# Mergen_Ground_Station_V2_0.net
KiCad netlist of a schematic drawn in EAGLE
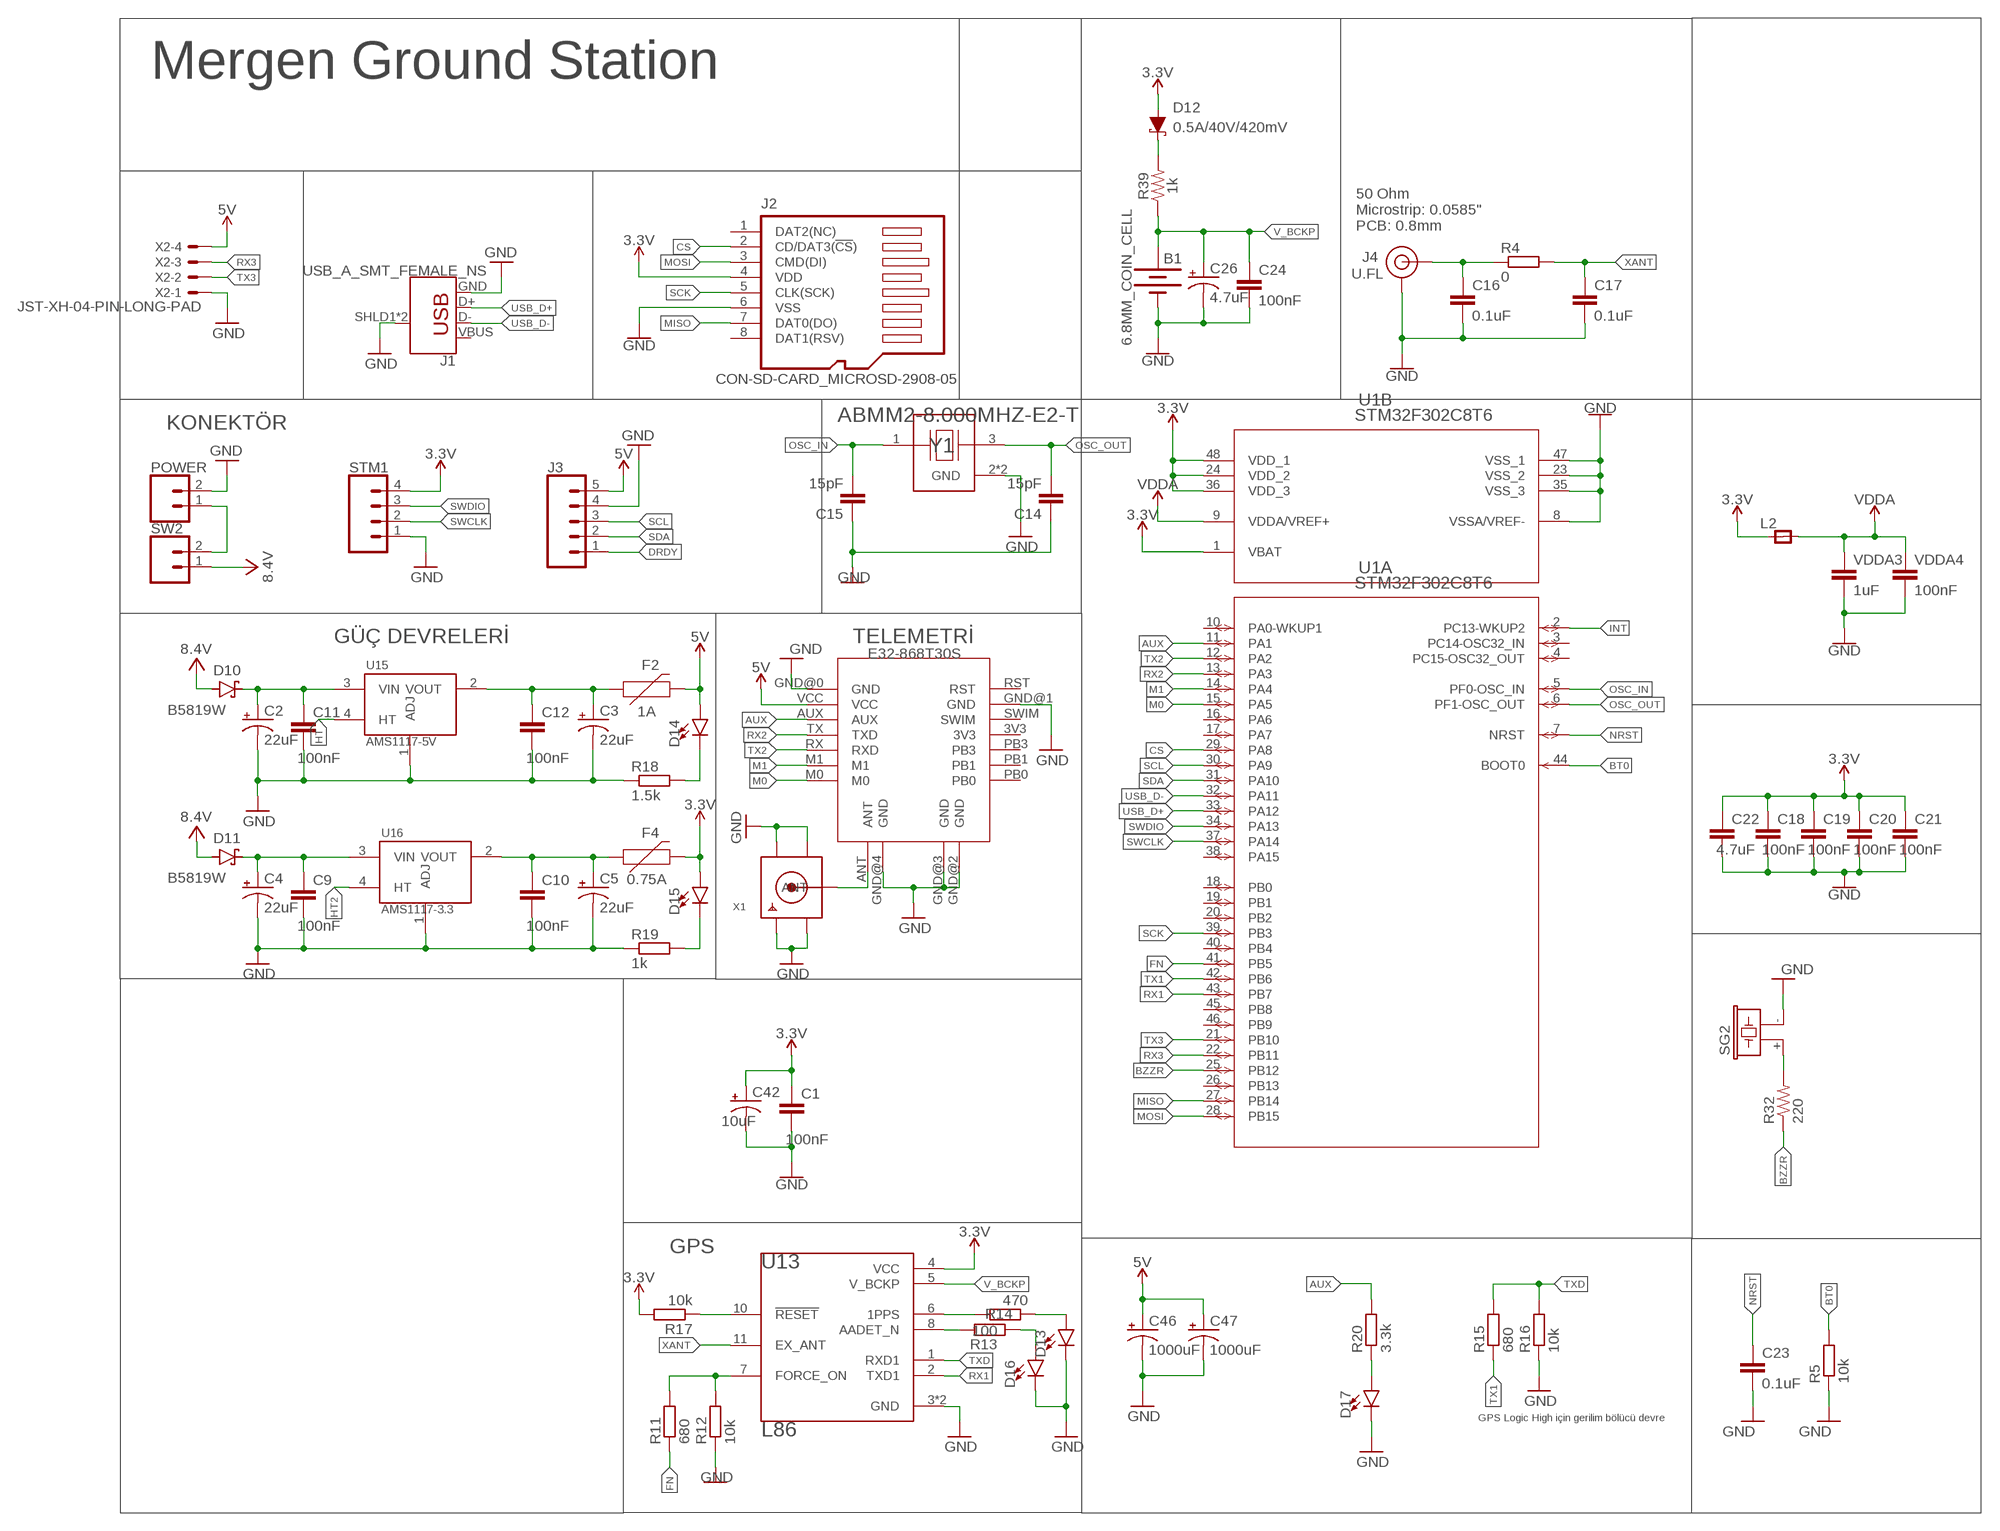
[diagram p0: schematic, sheet 1]

(export (version "E")
  (design (tool "Eeschema 10.0.6"))
  (components
    (comp (ref "B1")
      (value "6.8MM_COIN_CELL")
      (footprint "eagle-import:BATTCON-6.8MM")
      (libsource (lib "eagle-import") (part "BATTERY-6.8MM_SMD"))
    )
    (comp (ref "C1")
      (value "100nF")
      (footprint "eagle-import:C0603")
      (libsource (lib "eagle-import") (part "C-EUC0603"))
    )
    (comp (ref "C2")
      (value "22uF")
      (footprint "eagle-import:CT3528")
      (libsource (lib "eagle-import") (part "rcl_334_CPOL-USCT3528"))
    )
    (comp (ref "C3")
      (value "22uF")
      (footprint "eagle-import:CT3528")
      (libsource (lib "eagle-import") (part "rcl_334_CPOL-USCT3528"))
    )
    (comp (ref "C4")
      (value "22uF")
      (footprint "eagle-import:CT3528")
      (libsource (lib "eagle-import") (part "rcl_334_CPOL-USCT3528"))
    )
    (comp (ref "C5")
      (value "22uF")
      (footprint "eagle-import:CT3528")
      (libsource (lib "eagle-import") (part "rcl_334_CPOL-USCT3528"))
    )
    (comp (ref "C9")
      (value "100nF")
      (footprint "eagle-import:C0603")
      (libsource (lib "eagle-import") (part "C-EUC0603"))
    )
    (comp (ref "C10")
      (value "100nF")
      (footprint "eagle-import:C0603")
      (libsource (lib "eagle-import") (part "C-EUC0603"))
    )
    (comp (ref "C11")
      (value "100nF")
      (footprint "eagle-import:C0603")
      (libsource (lib "eagle-import") (part "C-EUC0603"))
    )
    (comp (ref "C12")
      (value "100nF")
      (footprint "eagle-import:C0603")
      (libsource (lib "eagle-import") (part "C-EUC0603"))
    )
    (comp (ref "C14")
      (value "15pF")
      (footprint "eagle-import:C0603")
      (libsource (lib "eagle-import") (part "C-EUC0603"))
    )
    (comp (ref "C15")
      (value "15pF")
      (footprint "eagle-import:C0603")
      (libsource (lib "eagle-import") (part "C-EUC0603"))
    )
    (comp (ref "C16")
      (value "0.1uF")
      (footprint "eagle-import:C0603")
      (libsource (lib "eagle-import") (part "C-EUC0603"))
    )
    (comp (ref "C17")
      (value "0.1uF")
      (footprint "eagle-import:C0603")
      (libsource (lib "eagle-import") (part "C-EUC0603"))
    )
    (comp (ref "C18")
      (value "100nF")
      (footprint "eagle-import:C0603")
      (libsource (lib "eagle-import") (part "C-EUC0603"))
    )
    (comp (ref "C19")
      (value "100nF")
      (footprint "eagle-import:C0603")
      (libsource (lib "eagle-import") (part "C-EUC0603"))
    )
    (comp (ref "C20")
      (value "100nF")
      (footprint "eagle-import:C0603")
      (libsource (lib "eagle-import") (part "C-EUC0603"))
    )
    (comp (ref "C21")
      (value "100nF")
      (footprint "eagle-import:C0603")
      (libsource (lib "eagle-import") (part "C-EUC0603"))
    )
    (comp (ref "C22")
      (value "4.7uF")
      (footprint "eagle-import:C0603")
      (libsource (lib "eagle-import") (part "C-EUC0603"))
    )
    (comp (ref "C23")
      (value "0.1uF")
      (footprint "eagle-import:C0603")
      (libsource (lib "eagle-import") (part "C-EUC0603"))
    )
    (comp (ref "C24")
      (value "100nF")
      (footprint "eagle-import:C0603")
      (libsource (lib "eagle-import") (part "C-EUC0603"))
    )
    (comp (ref "C26")
      (value "4.7uF")
      (footprint "eagle-import:A_3216-18R")
      (libsource (lib "eagle-import") (part "rcl_334_CPOL-USA/3216-18R"))
    )
    (comp (ref "C42")
      (value "10uF")
      (footprint "eagle-import:EIA3216")
      (libsource (lib "eagle-import") (part "10UF-POLAR-EIA3216-16V-10%(TANT)"))
    )
    (comp (ref "C46")
      (value "1000uF")
      (footprint "eagle-import:150CLZ-1010")
      (libsource (lib "eagle-import") (part "CPOL-US150CLZ-1010"))
    )
    (comp (ref "C47")
      (value "1000uF")
      (footprint "eagle-import:150CLZ-1010")
      (libsource (lib "eagle-import") (part "CPOL-US150CLZ-1010"))
    )
    (comp (ref "D10")
      (value "B5819W")
      (footprint "eagle-import:SODFL3718X115")
      (fields (field (name "MANUFACTURER") "ON Semiconductor") (field (name "MPN") "MBR0520LT1G"))
      (libsource (lib "eagle-import") (part "SCHOTTKY_DO-219MBR0520LT1G"))
    )
    (comp (ref "D11")
      (value "B5819W")
      (footprint "eagle-import:SODFL3718X115")
      (fields (field (name "MANUFACTURER") "ON Semiconductor") (field (name "MPN") "MBR0520LT1G"))
      (libsource (lib "eagle-import") (part "SCHOTTKY_DO-219MBR0520LT1G"))
    )
    (comp (ref "D12")
      (value "0.5A/40V/420mV")
      (footprint "eagle-import:SOD-323")
      (libsource (lib "eagle-import") (part "DIODE-SCHOTTKY-PMEG4005EJ"))
    )
    (comp (ref "D13")
      (value "LED0603")
      (footprint "eagle-import:LED-0603")
      (libsource (lib "eagle-import") (part "LED0603"))
    )
    (comp (ref "D14")
      (value "LED0603")
      (footprint "eagle-import:LED-0603")
      (libsource (lib "eagle-import") (part "LED0603"))
    )
    (comp (ref "D15")
      (value "LED0603")
      (footprint "eagle-import:LED-0603")
      (libsource (lib "eagle-import") (part "LED0603"))
    )
    (comp (ref "D16")
      (value "LED0603")
      (footprint "eagle-import:LED-0603")
      (libsource (lib "eagle-import") (part "LED0603"))
    )
    (comp (ref "D17")
      (value "LED0603")
      (footprint "eagle-import:LED-0603")
      (libsource (lib "eagle-import") (part "LED0603"))
    )
    (comp (ref "F2")
      (value "1A")
      (footprint "eagle-import:1206")
      (libsource (lib "eagle-import") (part "PPTC_HALF-AMP"))
    )
    (comp (ref "F4")
      (value "0.75A")
      (footprint "eagle-import:1206")
      (libsource (lib "eagle-import") (part "PPTC_HALF-AMP"))
    )
    (comp (ref "J1")
      (value "USB_A_SMT_FEMALE_NS")
      (footprint "eagle-import:USB-A-S-NOSILK-FEMALE")
      (libsource (lib "eagle-import") (part "USB_A_SMT_FEMALE_NS"))
    )
    (comp (ref "J2")
      (value "CON-SD-CARD_MICROSD-2908-05")
      (footprint "eagle-import:CON-SD-CARD_2908-05")
      (libsource (lib "eagle-import") (part "CON-SD-CARD_MICROSD-2908-05"))
    )
    (comp (ref "J3")
      (value "CONN_05LOCK_LONGPADS")
      (footprint "eagle-import:1X05_LOCK_LONGPADS")
      (libsource (lib "eagle-import") (part "CONN_05LOCK_LONGPADS"))
    )
    (comp (ref "J4")
      (value "U.FL")
      (footprint "eagle-import:U.FL")
      (libsource (lib "eagle-import") (part "U.FL2PIN"))
    )
    (comp (ref "L2")
      (value "RC-MASTER-SMD_FB_0805MP")
      (footprint "eagle-import:RC-MASTER-SMD_L0805MP")
      (libsource (lib "eagle-import") (part "RC-MASTER-SMD_FB_0805MP"))
    )
    (comp (ref "POWER")
      (value "CONN_023.5MM-NO_SILK")
      (footprint "eagle-import:SCREWTERMINAL-3.5MM-2-NS")
      (libsource (lib "eagle-import") (part "CONN_023.5MM-NO_SILK"))
    )
    (comp (ref "R4")
      (value "0")
      (footprint "eagle-import:R0603")
      (libsource (lib "eagle-import") (part "R-EU_R0603"))
    )
    (comp (ref "R5")
      (value "10k")
      (footprint "eagle-import:R0603")
      (libsource (lib "eagle-import") (part "R-EU_R0603"))
    )
    (comp (ref "R11")
      (value "680")
      (footprint "eagle-import:R0603")
      (libsource (lib "eagle-import") (part "R-EU_R0603"))
    )
    (comp (ref "R12")
      (value "10k")
      (footprint "eagle-import:R0603")
      (libsource (lib "eagle-import") (part "R-EU_R0603"))
    )
    (comp (ref "R13")
      (value "100")
      (footprint "eagle-import:R0603")
      (libsource (lib "eagle-import") (part "R-EU_R0603"))
    )
    (comp (ref "R14")
      (value "470")
      (footprint "eagle-import:R0603")
      (libsource (lib "eagle-import") (part "R-EU_R0603"))
    )
    (comp (ref "R15")
      (value "680")
      (footprint "eagle-import:R0603")
      (libsource (lib "eagle-import") (part "R-EU_R0603"))
    )
    (comp (ref "R16")
      (value "10k")
      (footprint "eagle-import:R0603")
      (libsource (lib "eagle-import") (part "R-EU_R0603"))
    )
    (comp (ref "R17")
      (value "10k")
      (footprint "eagle-import:R0603")
      (libsource (lib "eagle-import") (part "R-EU_R0603"))
    )
    (comp (ref "R18")
      (value "1.5k")
      (footprint "eagle-import:R0603")
      (libsource (lib "eagle-import") (part "R-EU_R0603"))
    )
    (comp (ref "R19")
      (value "1k")
      (footprint "eagle-import:R0603")
      (libsource (lib "eagle-import") (part "R-EU_R0603"))
    )
    (comp (ref "R20")
      (value "3.3k")
      (footprint "eagle-import:R0603")
      (libsource (lib "eagle-import") (part "R-EU_R0603"))
    )
    (comp (ref "R32")
      (value "220")
      (footprint "eagle-import:0603")
      (libsource (lib "eagle-import") (part "0OHM-0603-1/10W-5%"))
    )
    (comp (ref "R39")
      (value "1k")
      (footprint "eagle-import:0603")
      (libsource (lib "eagle-import") (part "1KOHM-0603-1/10W-1%"))
    )
    (comp (ref "SG2")
      (value "F/CM12P")
      (footprint "eagle-import:F_CM12P")
      (libsource (lib "eagle-import") (part "F/CM12P"))
    )
    (comp (ref "STM1")
      (value "CONN_04")
      (footprint "eagle-import:1X04")
      (libsource (lib "eagle-import") (part "CONN_04"))
    )
    (comp (ref "SW2")
      (value "CONN_023.5MM-NO_SILK")
      (footprint "eagle-import:SCREWTERMINAL-3.5MM-2-NS")
      (libsource (lib "eagle-import") (part "CONN_023.5MM-NO_SILK"))
    )
    (comp (ref "U1")
      (value "STM32F302C8T6")
      (footprint "eagle-import:LQFP48-7X7MM")
      (fields (field (name "COPYRIGHT") "Copyright (C) 2018 Accelerated Designs. All rights reserved"))
      (libsource (lib "eagle-import") (part "STM32F302C8T6"))
    )
    (comp (ref "U13")
      (value "L86")
      (footprint "eagle-import:XCVR_L86")
      (fields (field (name "MF") "Quectel"))
      (libsource (lib "eagle-import") (part "L86"))
    )
    (comp (ref "U14")
      (value "E32-868T30S")
      (footprint "eagle-import:E32-868T30S")
      (libsource (lib "eagle-import") (part "E32-868T30S"))
    )
    (comp (ref "U15")
      (value "AMS1117-5V")
      (footprint "eagle-import:SOT229P700X180-4N")
      (fields (field (name "MF") "Advanced Monolithic Systems") (field (name "MP") "AMS1117-3.3"))
      (libsource (lib "eagle-import") (part "AMS1117-3.3"))
    )
    (comp (ref "U16")
      (value "AMS1117-3.3")
      (footprint "eagle-import:SOT229P700X180-4N")
      (fields (field (name "MF") "Advanced Monolithic Systems"))
      (libsource (lib "eagle-import") (part "AMS1117-3.3"))
    )
    (comp (ref "VDDA3")
      (value "1uF")
      (footprint "eagle-import:0603")
      (libsource (lib "eagle-import") (part "0.1UF-0603-25V-(+80/-20%)"))
    )
    (comp (ref "VDDA4")
      (value "100nF")
      (footprint "eagle-import:0603")
      (libsource (lib "eagle-import") (part "0.1UF-0603-25V-(+80/-20%)"))
    )
    (comp (ref "X1")
      (value "SMACONNECTOR")
      (footprint "eagle-import:SMA90_DIP")
      (libsource (lib "eagle-import") (part "SMACONNECTOR"))
    )
    (comp (ref "X2")
      (value "JST-XH-04-PIN-LONG-PAD")
      (footprint "eagle-import:JST-XH-04-PACKAGE-LONG-PAD")
      (libsource (lib "eagle-import") (part "JST-XH-04-PIN-LONG-PAD"))
    )
    (comp (ref "Y1")
      (value "ABMM2-8.000MHZ-E2-T")
      (footprint "eagle-import:XTAL_ABMM2-8.000MHZ-E2-T")
      (fields (field (name "MF") "Abracon"))
      (libsource (lib "eagle-import") (part "ABMM2-8.000MHZ-E2-T"))
    )
  )
  (nets
    (net (code "1") (name "/VBUS") (class "Default")
      (node (ref "J1") (pin "VBUS") (pinfunction "VBUS_VBUS") (pintype "power_in"))
    )
    (net (code "2") (name "3.3V") (class "Default")
      (node (ref "C1") (pin "1") (pinfunction "1_1") (pintype "passive"))
      (node (ref "C18") (pin "1") (pinfunction "1_1") (pintype "passive"))
      (node (ref "C19") (pin "1") (pinfunction "1_1") (pintype "passive"))
      (node (ref "C20") (pin "1") (pinfunction "1_1") (pintype "passive"))
      (node (ref "C21") (pin "1") (pinfunction "1_1") (pintype "passive"))
      (node (ref "C22") (pin "1") (pinfunction "1_1") (pintype "passive"))
      (node (ref "C42") (pin "+") (pinfunction "+_+") (pintype "passive"))
      (node (ref "D12") (pin "A") (pinfunction "A_A") (pintype "passive"))
      (node (ref "D15") (pin "A") (pinfunction "A_A") (pintype "passive"))
      (node (ref "F4") (pin "2") (pinfunction "2_2") (pintype "bidirectional"))
      (node (ref "J2") (pin "4") (pinfunction "VDD_4") (pintype "bidirectional"))
      (node (ref "L2") (pin "1") (pinfunction "1_1") (pintype "passive"))
      (node (ref "R17") (pin "2") (pinfunction "2_2") (pintype "passive"))
      (node (ref "STM1") (pin "4") (pinfunction "4_4") (pintype "passive"))
      (node (ref "U1") (pin "1") (pinfunction "VBAT_1") (pintype "power_in"))
      (node (ref "U1") (pin "24") (pinfunction "VDD_2_24") (pintype "power_in"))
      (node (ref "U1") (pin "36") (pinfunction "VDD_3_36") (pintype "power_in"))
      (node (ref "U1") (pin "48") (pinfunction "VDD_1_48") (pintype "power_in"))
      (node (ref "U13") (pin "4") (pinfunction "VCC_4") (pintype "power_in"))
    )
    (net (code "3") (name "5V") (class "Default")
      (node (ref "C46") (pin "+") (pinfunction "+_+") (pintype "passive"))
      (node (ref "C47") (pin "+") (pinfunction "+_+") (pintype "passive"))
      (node (ref "D14") (pin "A") (pinfunction "A_A") (pintype "passive"))
      (node (ref "F2") (pin "2") (pinfunction "2_2") (pintype "bidirectional"))
      (node (ref "J3") (pin "5") (pinfunction "5_5") (pintype "passive"))
      (node (ref "U14") (pin "VCC") (pinfunction "VCC_VCC") (pintype "bidirectional"))
      (node (ref "X2") (pin "4") (pinfunction "S_4") (pintype "passive"))
    )
    (net (code "4") (name "8.4V") (class "Default")
      (node (ref "D10") (pin "2") (pinfunction "A_2") (pintype "passive"))
      (node (ref "D11") (pin "2") (pinfunction "A_2") (pintype "passive"))
      (node (ref "SW2") (pin "1") (pinfunction "1_1") (pintype "passive"))
    )
    (net (code "5") (name "AUX") (class "Default")
      (node (ref "R20") (pin "2") (pinfunction "2_2") (pintype "passive"))
      (node (ref "U1") (pin "11") (pinfunction "PA1_11") (pintype "bidirectional"))
      (node (ref "U14") (pin "AUX") (pinfunction "AUX_AUX") (pintype "bidirectional"))
    )
    (net (code "6") (name "BT0") (class "Default")
      (node (ref "R5") (pin "2") (pinfunction "2_2") (pintype "passive"))
      (node (ref "U1") (pin "44") (pinfunction "BOOT0_44") (pintype "input"))
    )
    (net (code "7") (name "BZZR") (class "Default")
      (node (ref "R32") (pin "1") (pinfunction "1_1") (pintype "passive"))
      (node (ref "U1") (pin "25") (pinfunction "PB12_25") (pintype "bidirectional"))
    )
    (net (code "8") (name "CS") (class "Default")
      (node (ref "J2") (pin "2") (pinfunction "CD/DAT3(~{CS})_2") (pintype "bidirectional"))
      (node (ref "U1") (pin "29") (pinfunction "PA8_29") (pintype "bidirectional"))
    )
    (net (code "9") (name "DRDY") (class "Default")
      (node (ref "J3") (pin "1") (pinfunction "1_1") (pintype "passive"))
    )
    (net (code "10") (name "FN") (class "Default")
      (node (ref "R11") (pin "1") (pinfunction "1_1") (pintype "passive"))
      (node (ref "U1") (pin "41") (pinfunction "PB5_41") (pintype "bidirectional"))
    )
    (net (code "11") (name "GND") (class "Default")
      (node (ref "B1") (pin "-") (pinfunction "-_-") (pintype "power_in"))
      (node (ref "C1") (pin "2") (pinfunction "2_2") (pintype "passive"))
      (node (ref "C10") (pin "2") (pinfunction "2_2") (pintype "passive"))
      (node (ref "C11") (pin "2") (pinfunction "2_2") (pintype "passive"))
      (node (ref "C12") (pin "2") (pinfunction "2_2") (pintype "passive"))
      (node (ref "C14") (pin "1") (pinfunction "1_1") (pintype "passive"))
      (node (ref "C15") (pin "1") (pinfunction "1_1") (pintype "passive"))
      (node (ref "C16") (pin "2") (pinfunction "2_2") (pintype "passive"))
      (node (ref "C17") (pin "2") (pinfunction "2_2") (pintype "passive"))
      (node (ref "C18") (pin "2") (pinfunction "2_2") (pintype "passive"))
      (node (ref "C19") (pin "2") (pinfunction "2_2") (pintype "passive"))
      (node (ref "C2") (pin "-") (pinfunction "-_-") (pintype "passive"))
      (node (ref "C20") (pin "2") (pinfunction "2_2") (pintype "passive"))
      (node (ref "C21") (pin "2") (pinfunction "2_2") (pintype "passive"))
      (node (ref "C22") (pin "2") (pinfunction "2_2") (pintype "passive"))
      (node (ref "C23") (pin "2") (pinfunction "2_2") (pintype "passive"))
      (node (ref "C24") (pin "2") (pinfunction "2_2") (pintype "passive"))
      (node (ref "C26") (pin "-") (pinfunction "-_-") (pintype "passive"))
      (node (ref "C3") (pin "-") (pinfunction "-_-") (pintype "passive"))
      (node (ref "C4") (pin "-") (pinfunction "-_-") (pintype "passive"))
      (node (ref "C42") (pin "-") (pinfunction "-_-") (pintype "passive"))
      (node (ref "C46") (pin "-") (pinfunction "-_-") (pintype "passive"))
      (node (ref "C47") (pin "-") (pinfunction "-_-") (pintype "passive"))
      (node (ref "C5") (pin "-") (pinfunction "-_-") (pintype "passive"))
      (node (ref "C9") (pin "2") (pinfunction "2_2") (pintype "passive"))
      (node (ref "D13") (pin "C") (pinfunction "C_C") (pintype "passive"))
      (node (ref "D16") (pin "C") (pinfunction "C_C") (pintype "passive"))
      (node (ref "D17") (pin "C") (pinfunction "C_C") (pintype "passive"))
      (node (ref "J1") (pin "GND") (pinfunction "GND_GND") (pintype "power_in"))
      (node (ref "J1") (pin "SHLD1") (pinfunction "SHIELD_SHLD1") (pintype "bidirectional"))
      (node (ref "J1") (pin "SHLD2") (pinfunction "SHIELD_SHLD2") (pintype "bidirectional"))
      (node (ref "J2") (pin "6") (pinfunction "VSS_6") (pintype "bidirectional"))
      (node (ref "J3") (pin "4") (pinfunction "4_4") (pintype "passive"))
      (node (ref "J4") (pin "1") (pinfunction "GND_1") (pintype "bidirectional"))
      (node (ref "J4") (pin "2") (pinfunction "GND_2") (pintype "bidirectional"))
      (node (ref "POWER") (pin "2") (pinfunction "2_2") (pintype "passive"))
      (node (ref "R12") (pin "1") (pinfunction "1_1") (pintype "passive"))
      (node (ref "R16") (pin "1") (pinfunction "1_1") (pintype "passive"))
      (node (ref "R18") (pin "1") (pinfunction "1_1") (pintype "passive"))
      (node (ref "R19") (pin "1") (pinfunction "1_1") (pintype "passive"))
      (node (ref "R5") (pin "1") (pinfunction "1_1") (pintype "passive"))
      (node (ref "SG2") (pin "-") (pinfunction "2_-") (pintype "passive"))
      (node (ref "STM1") (pin "1") (pinfunction "1_1") (pintype "passive"))
      (node (ref "U1") (pin "23") (pinfunction "VSS_2_23") (pintype "power_in"))
      (node (ref "U1") (pin "35") (pinfunction "VSS_3_35") (pintype "power_in"))
      (node (ref "U1") (pin "47") (pinfunction "VSS_1_47") (pintype "power_in"))
      (node (ref "U1") (pin "8") (pinfunction "VSSA/VREF-_8") (pintype "power_in"))
      (node (ref "U13") (pin "12") (pinfunction "GND_12") (pintype "passive"))
      (node (ref "U13") (pin "3") (pinfunction "GND_3") (pintype "passive"))
      (node (ref "U14") (pin "GND@0") (pinfunction "GND_GND@0") (pintype "bidirectional"))
      (node (ref "U14") (pin "GND@1") (pinfunction "GND_GND@1") (pintype "bidirectional"))
      (node (ref "U14") (pin "GND@2") (pinfunction "GND_GND@2") (pintype "bidirectional"))
      (node (ref "U14") (pin "GND@3") (pinfunction "GND_GND@3") (pintype "bidirectional"))
      (node (ref "U14") (pin "GND@4") (pinfunction "GND_GND@4") (pintype "bidirectional"))
      (node (ref "U15") (pin "1") (pinfunction "ADJ_1") (pintype "power_in"))
      (node (ref "U16") (pin "1") (pinfunction "ADJ_1") (pintype "power_in"))
      (node (ref "VDDA3") (pin "2") (pinfunction "2_2") (pintype "passive"))
      (node (ref "VDDA4") (pin "2") (pinfunction "2_2") (pintype "passive"))
      (node (ref "X1") (pin "GND1") (pinfunction "GND1_GND1") (pintype "power_in"))
      (node (ref "X1") (pin "GND2") (pinfunction "GND2_GND2") (pintype "power_in"))
      (node (ref "X1") (pin "GND3") (pinfunction "GND3_GND3") (pintype "power_in"))
      (node (ref "X1") (pin "GND4") (pinfunction "GND4_GND4") (pintype "power_in"))
      (node (ref "X2") (pin "1") (pinfunction "S_1") (pintype "passive"))
      (node (ref "Y1") (pin "2") (pinfunction "GND_2") (pintype "power_in"))
      (node (ref "Y1") (pin "4") (pinfunction "GND_4") (pintype "power_in"))
    )
    (net (code "12") (name "HT") (class "Default")
      (node (ref "U15") (pin "4") (pinfunction "HT_4") (pintype "bidirectional"))
    )
    (net (code "13") (name "HT2") (class "Default")
      (node (ref "U16") (pin "4") (pinfunction "HT_4") (pintype "bidirectional"))
    )
    (net (code "14") (name "INT") (class "Default")
      (node (ref "U1") (pin "2") (pinfunction "PC13-WKUP2_2") (pintype "bidirectional"))
    )
    (net (code "15") (name "M0") (class "Default")
      (node (ref "U1") (pin "15") (pinfunction "PA5_15") (pintype "bidirectional"))
      (node (ref "U14") (pin "M0") (pinfunction "M0_M0") (pintype "bidirectional"))
    )
    (net (code "16") (name "M1") (class "Default")
      (node (ref "U1") (pin "14") (pinfunction "PA4_14") (pintype "bidirectional"))
      (node (ref "U14") (pin "M1") (pinfunction "M1_M1") (pintype "bidirectional"))
    )
    (net (code "17") (name "MISO") (class "Default")
      (node (ref "J2") (pin "7") (pinfunction "DAT0(DO)_7") (pintype "bidirectional"))
      (node (ref "U1") (pin "27") (pinfunction "PB14_27") (pintype "bidirectional"))
    )
    (net (code "18") (name "MOSI") (class "Default")
      (node (ref "J2") (pin "3") (pinfunction "CMD(DI)_3") (pintype "bidirectional"))
      (node (ref "U1") (pin "28") (pinfunction "PB15_28") (pintype "bidirectional"))
    )
    (net (code "19") (name "NRST") (class "Default")
      (node (ref "C23") (pin "1") (pinfunction "1_1") (pintype "passive"))
      (node (ref "U1") (pin "7") (pinfunction "NRST_7") (pintype "bidirectional"))
    )
    (net (code "20") (name "Net-(D10-C)") (class "Default")
      (node (ref "C11") (pin "1") (pinfunction "1_1") (pintype "passive"))
      (node (ref "C2") (pin "+") (pinfunction "+_+") (pintype "passive"))
      (node (ref "D10") (pin "1") (pinfunction "C_1") (pintype "passive"))
      (node (ref "U15") (pin "3") (pinfunction "VIN_3") (pintype "input"))
    )
    (net (code "21") (name "Net-(D11-C)") (class "Default")
      (node (ref "C4") (pin "+") (pinfunction "+_+") (pintype "passive"))
      (node (ref "C9") (pin "1") (pinfunction "1_1") (pintype "passive"))
      (node (ref "D11") (pin "1") (pinfunction "C_1") (pintype "passive"))
      (node (ref "U16") (pin "3") (pinfunction "VIN_3") (pintype "input"))
    )
    (net (code "22") (name "Net-(D12-PadC)") (class "Default")
      (node (ref "D12") (pin "C") (pinfunction "C_C") (pintype "passive"))
      (node (ref "R39") (pin "2") (pinfunction "2_2") (pintype "passive"))
    )
    (net (code "23") (name "Net-(D13-PadA)") (class "Default")
      (node (ref "D13") (pin "A") (pinfunction "A_A") (pintype "passive"))
      (node (ref "R14") (pin "1") (pinfunction "1_1") (pintype "passive"))
    )
    (net (code "24") (name "Net-(D14-PadC)") (class "Default")
      (node (ref "D14") (pin "C") (pinfunction "C_C") (pintype "passive"))
      (node (ref "R18") (pin "2") (pinfunction "2_2") (pintype "passive"))
    )
    (net (code "25") (name "Net-(D15-PadC)") (class "Default")
      (node (ref "D15") (pin "C") (pinfunction "C_C") (pintype "passive"))
      (node (ref "R19") (pin "2") (pinfunction "2_2") (pintype "passive"))
    )
    (net (code "26") (name "Net-(D16-PadA)") (class "Default")
      (node (ref "D16") (pin "A") (pinfunction "A_A") (pintype "passive"))
      (node (ref "R13") (pin "1") (pinfunction "1_1") (pintype "passive"))
    )
    (net (code "27") (name "Net-(D17-PadA)") (class "Default")
      (node (ref "D17") (pin "A") (pinfunction "A_A") (pintype "passive"))
      (node (ref "R20") (pin "1") (pinfunction "1_1") (pintype "passive"))
    )
    (net (code "28") (name "Net-(J4-SIGNAL)") (class "Default")
      (node (ref "C16") (pin "1") (pinfunction "1_1") (pintype "passive"))
      (node (ref "J4") (pin "FEED") (pinfunction "SIGNAL_FEED") (pintype "bidirectional"))
      (node (ref "R4") (pin "1") (pinfunction "1_1") (pintype "passive"))
    )
    (net (code "29") (name "Net-(POWER-Pad1)") (class "Default")
      (node (ref "POWER") (pin "1") (pinfunction "1_1") (pintype "passive"))
      (node (ref "SW2") (pin "2") (pinfunction "2_2") (pintype "passive"))
    )
    (net (code "30") (name "Net-(SG2-1)") (class "Default")
      (node (ref "R32") (pin "2") (pinfunction "2_2") (pintype "passive"))
      (node (ref "SG2") (pin "+") (pinfunction "1_+") (pintype "passive"))
    )
    (net (code "31") (name "Net-(U13-1PPS)") (class "Default")
      (node (ref "R14") (pin "2") (pinfunction "2_2") (pintype "passive"))
      (node (ref "U13") (pin "6") (pinfunction "1PPS_6") (pintype "output"))
    )
    (net (code "32") (name "Net-(U13-AADET_N)") (class "Default")
      (node (ref "R13") (pin "2") (pinfunction "2_2") (pintype "passive"))
      (node (ref "U13") (pin "8") (pinfunction "AADET_N_8") (pintype "output"))
    )
    (net (code "33") (name "Net-(U13-FORCE_ON)") (class "Default")
      (node (ref "R11") (pin "2") (pinfunction "2_2") (pintype "passive"))
      (node (ref "R12") (pin "2") (pinfunction "2_2") (pintype "passive"))
      (node (ref "U13") (pin "7") (pinfunction "FORCE_ON_7") (pintype "input"))
    )
    (net (code "34") (name "Net-(U13-~{RESET})") (class "Default")
      (node (ref "R17") (pin "1") (pinfunction "1_1") (pintype "passive"))
      (node (ref "U13") (pin "10") (pinfunction "~{RESET}_10") (pintype "input"))
    )
    (net (code "35") (name "Net-(U15-VOUT)") (class "Default")
      (node (ref "C12") (pin "1") (pinfunction "1_1") (pintype "passive"))
      (node (ref "C3") (pin "+") (pinfunction "+_+") (pintype "passive"))
      (node (ref "F2") (pin "1") (pinfunction "1_1") (pintype "bidirectional"))
      (node (ref "U15") (pin "2") (pinfunction "VOUT_2") (pintype "output"))
    )
    (net (code "36") (name "Net-(U16-VOUT)") (class "Default")
      (node (ref "C10") (pin "1") (pinfunction "1_1") (pintype "passive"))
      (node (ref "C5") (pin "+") (pinfunction "+_+") (pintype "passive"))
      (node (ref "F4") (pin "1") (pinfunction "1_1") (pintype "bidirectional"))
      (node (ref "U16") (pin "2") (pinfunction "VOUT_2") (pintype "output"))
    )
    (net (code "37") (name "Net-(X1-ANT)") (class "Default")
      (node (ref "U14") (pin "ANT") (pinfunction "ANT_ANT") (pintype "bidirectional"))
      (node (ref "X1") (pin "ANTENNA") (pinfunction "ANT_ANTENNA") (pintype "bidirectional"))
    )
    (net (code "38") (name "OSC_IN") (class "Default")
      (node (ref "C15") (pin "2") (pinfunction "2_2") (pintype "passive"))
      (node (ref "U1") (pin "5") (pinfunction "PF0-OSC_IN_5") (pintype "bidirectional"))
      (node (ref "Y1") (pin "1") (pinfunction "1_1") (pintype "passive"))
    )
    (net (code "39") (name "OSC_OUT") (class "Default")
      (node (ref "C14") (pin "2") (pinfunction "2_2") (pintype "passive"))
      (node (ref "U1") (pin "6") (pinfunction "PF1-OSC_OUT_6") (pintype "bidirectional"))
      (node (ref "Y1") (pin "3") (pinfunction "3_3") (pintype "passive"))
    )
    (net (code "40") (name "RX1") (class "Default")
      (node (ref "U1") (pin "43") (pinfunction "PB7_43") (pintype "bidirectional"))
      (node (ref "U13") (pin "2") (pinfunction "TXD1_2") (pintype "output"))
    )
    (net (code "41") (name "RX2") (class "Default")
      (node (ref "U1") (pin "13") (pinfunction "PA3_13") (pintype "bidirectional"))
      (node (ref "U14") (pin "TX") (pinfunction "TXD_TX") (pintype "bidirectional"))
    )
    (net (code "42") (name "RX3") (class "Default")
      (node (ref "U1") (pin "22") (pinfunction "PB11_22") (pintype "bidirectional"))
      (node (ref "X2") (pin "3") (pinfunction "S_3") (pintype "passive"))
    )
    (net (code "43") (name "SCK") (class "Default")
      (node (ref "J2") (pin "5") (pinfunction "CLK(SCK)_5") (pintype "bidirectional"))
      (node (ref "U1") (pin "39") (pinfunction "PB3_39") (pintype "bidirectional"))
    )
    (net (code "44") (name "SCL") (class "Default")
      (node (ref "J3") (pin "3") (pinfunction "3_3") (pintype "passive"))
      (node (ref "U1") (pin "30") (pinfunction "PA9_30") (pintype "bidirectional"))
    )
    (net (code "45") (name "SDA") (class "Default")
      (node (ref "J3") (pin "2") (pinfunction "2_2") (pintype "passive"))
      (node (ref "U1") (pin "31") (pinfunction "PA10_31") (pintype "bidirectional"))
    )
    (net (code "46") (name "SWCLK") (class "Default")
      (node (ref "STM1") (pin "2") (pinfunction "2_2") (pintype "passive"))
      (node (ref "U1") (pin "37") (pinfunction "PA14_37") (pintype "bidirectional"))
    )
    (net (code "47") (name "SWDIO") (class "Default")
      (node (ref "STM1") (pin "3") (pinfunction "3_3") (pintype "passive"))
      (node (ref "U1") (pin "34") (pinfunction "PA13_34") (pintype "bidirectional"))
    )
    (net (code "48") (name "TX1") (class "Default")
      (node (ref "R15") (pin "1") (pinfunction "1_1") (pintype "passive"))
      (node (ref "U1") (pin "42") (pinfunction "PB6_42") (pintype "bidirectional"))
    )
    (net (code "49") (name "TX2") (class "Default")
      (node (ref "U1") (pin "12") (pinfunction "PA2_12") (pintype "bidirectional"))
      (node (ref "U14") (pin "RX") (pinfunction "RXD_RX") (pintype "bidirectional"))
    )
    (net (code "50") (name "TX3") (class "Default")
      (node (ref "U1") (pin "21") (pinfunction "PB10_21") (pintype "bidirectional"))
      (node (ref "X2") (pin "2") (pinfunction "S_2") (pintype "passive"))
    )
    (net (code "51") (name "TXD") (class "Default")
      (node (ref "R15") (pin "2") (pinfunction "2_2") (pintype "passive"))
      (node (ref "R16") (pin "2") (pinfunction "2_2") (pintype "passive"))
      (node (ref "U13") (pin "1") (pinfunction "RXD1_1") (pintype "input"))
    )
    (net (code "52") (name "USB_D+") (class "Default")
      (node (ref "J1") (pin "D+") (pinfunction "D+_D+") (pintype "bidirectional"))
      (node (ref "U1") (pin "33") (pinfunction "PA12_33") (pintype "bidirectional"))
    )
    (net (code "53") (name "USB_D-") (class "Default")
      (node (ref "J1") (pin "D-") (pinfunction "D-_D-") (pintype "bidirectional"))
      (node (ref "U1") (pin "32") (pinfunction "PA11_32") (pintype "bidirectional"))
    )
    (net (code "54") (name "VDDA") (class "Default")
      (node (ref "L2") (pin "2") (pinfunction "2_2") (pintype "passive"))
      (node (ref "U1") (pin "9") (pinfunction "VDDA/VREF+_9") (pintype "power_in"))
      (node (ref "VDDA3") (pin "1") (pinfunction "1_1") (pintype "passive"))
      (node (ref "VDDA4") (pin "1") (pinfunction "1_1") (pintype "passive"))
    )
    (net (code "55") (name "V_BCKP") (class "Default")
      (node (ref "B1") (pin "+") (pinfunction "+_+") (pintype "power_in"))
      (node (ref "C24") (pin "1") (pinfunction "1_1") (pintype "passive"))
      (node (ref "C26") (pin "+") (pinfunction "+_+") (pintype "passive"))
      (node (ref "R39") (pin "1") (pinfunction "1_1") (pintype "passive"))
      (node (ref "U13") (pin "5") (pinfunction "V_BCKP_5") (pintype "power_in"))
    )
    (net (code "56") (name "XANT") (class "Default")
      (node (ref "C17") (pin "1") (pinfunction "1_1") (pintype "passive"))
      (node (ref "R4") (pin "2") (pinfunction "2_2") (pintype "passive"))
      (node (ref "U13") (pin "11") (pinfunction "EX_ANT_11") (pintype "input"))
    )
    (net (code "57") (name "unconnected-(J2B-DAT1(RSV)-Pad8)") (class "Default")
      (node (ref "J2") (pin "8") (pinfunction "DAT1(RSV)_8") (pintype "bidirectional"))
    )
    (net (code "58") (name "unconnected-(J2B-DAT2(NC)-Pad1)") (class "Default")
      (node (ref "J2") (pin "1") (pinfunction "DAT2(NC)_1") (pintype "bidirectional"))
    )
    (net (code "59") (name "unconnected-(U1A-PA0-WKUP1-Pad10)") (class "Default")
      (node (ref "U1") (pin "10") (pinfunction "PA0-WKUP1_10") (pintype "bidirectional"))
    )
    (net (code "60") (name "unconnected-(U1A-PA6-Pad16)") (class "Default")
      (node (ref "U1") (pin "16") (pinfunction "PA6_16") (pintype "bidirectional"))
    )
    (net (code "61") (name "unconnected-(U1A-PA7-Pad17)") (class "Default")
      (node (ref "U1") (pin "17") (pinfunction "PA7_17") (pintype "bidirectional"))
    )
    (net (code "62") (name "unconnected-(U1A-PA15-Pad38)") (class "Default")
      (node (ref "U1") (pin "38") (pinfunction "PA15_38") (pintype "bidirectional"))
    )
    (net (code "63") (name "unconnected-(U1A-PB0-Pad18)") (class "Default")
      (node (ref "U1") (pin "18") (pinfunction "PB0_18") (pintype "bidirectional"))
    )
    (net (code "64") (name "unconnected-(U1A-PB1-Pad19)") (class "Default")
      (node (ref "U1") (pin "19") (pinfunction "PB1_19") (pintype "bidirectional"))
    )
    (net (code "65") (name "unconnected-(U1A-PB2-Pad20)") (class "Default")
      (node (ref "U1") (pin "20") (pinfunction "PB2_20") (pintype "bidirectional"))
    )
    (net (code "66") (name "unconnected-(U1A-PB4-Pad40)") (class "Default")
      (node (ref "U1") (pin "40") (pinfunction "PB4_40") (pintype "bidirectional"))
    )
    (net (code "67") (name "unconnected-(U1A-PB8-Pad45)") (class "Default")
      (node (ref "U1") (pin "45") (pinfunction "PB8_45") (pintype "bidirectional"))
    )
    (net (code "68") (name "unconnected-(U1A-PB9-Pad46)") (class "Default")
      (node (ref "U1") (pin "46") (pinfunction "PB9_46") (pintype "bidirectional"))
    )
    (net (code "69") (name "unconnected-(U1A-PB13-Pad26)") (class "Default")
      (node (ref "U1") (pin "26") (pinfunction "PB13_26") (pintype "bidirectional"))
    )
    (net (code "70") (name "unconnected-(U1A-PC14-OSC32_IN-Pad3)") (class "Default")
      (node (ref "U1") (pin "3") (pinfunction "PC14-OSC32_IN_3") (pintype "bidirectional"))
    )
    (net (code "71") (name "unconnected-(U1A-PC15-OSC32_OUT-Pad4)") (class "Default")
      (node (ref "U1") (pin "4") (pinfunction "PC15-OSC32_OUT_4") (pintype "bidirectional"))
    )
    (net (code "72") (name "unconnected-(U14-Pad3V3)") (class "Default")
      (node (ref "U14") (pin "3V3") (pinfunction "3V3_3V3") (pintype "bidirectional"))
    )
    (net (code "73") (name "unconnected-(U14-PadPB0)") (class "Default")
      (node (ref "U14") (pin "PB0") (pinfunction "PB0_PB0") (pintype "bidirectional"))
    )
    (net (code "74") (name "unconnected-(U14-PadPB1)") (class "Default")
      (node (ref "U14") (pin "PB1") (pinfunction "PB1_PB1") (pintype "bidirectional"))
    )
    (net (code "75") (name "unconnected-(U14-PadPB3)") (class "Default")
      (node (ref "U14") (pin "PB3") (pinfunction "PB3_PB3") (pintype "bidirectional"))
    )
    (net (code "76") (name "unconnected-(U14-PadRST)") (class "Default")
      (node (ref "U14") (pin "RST") (pinfunction "RST_RST") (pintype "bidirectional"))
    )
    (net (code "77") (name "unconnected-(U14-PadSWIM)") (class "Default")
      (node (ref "U14") (pin "SWIM") (pinfunction "SWIM_SWIM") (pintype "bidirectional"))
    )
  )
)
